# LCD.net
KiCad netlist of a schematic drawn in Altium Designer
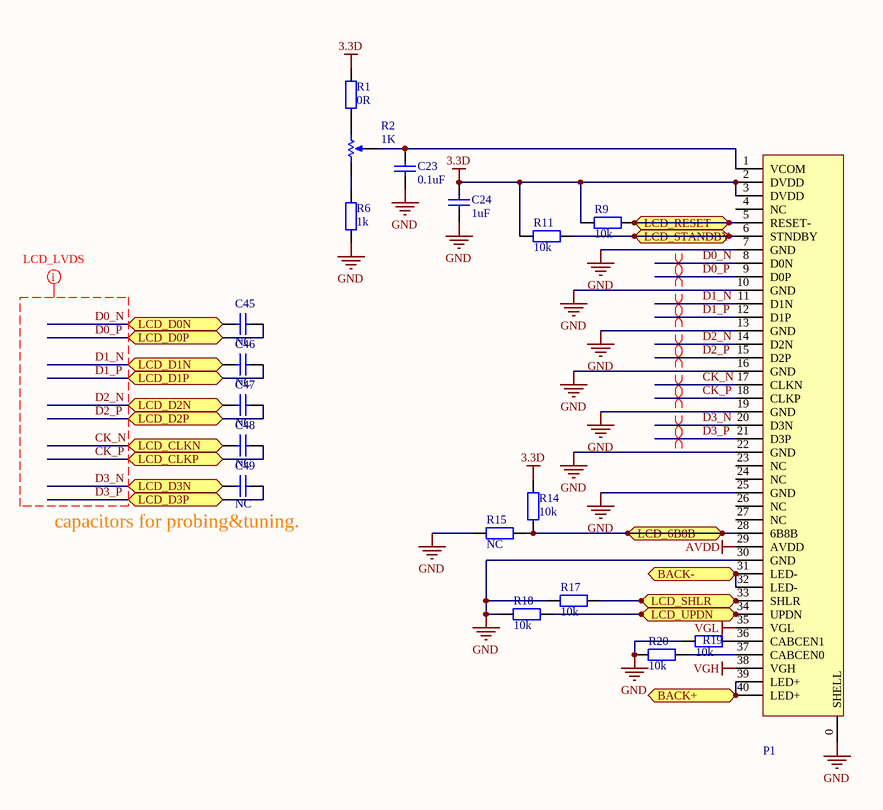
[diagram p0: LCD.SchDoc]

(export (version "E")
  (design (tool "Eeschema 10.0.6"))
  (components
    (comp (ref "C23")
      (value "0.1uF")
      (footprint "0402")
      (description "Capacitor")
      (fields (field (name "PUBLISHER") "Altium Limited"))
      (libsource (lib "RTC6705") (part "Cap"))
    )
    (comp (ref "C24")
      (value "1uF")
      (footprint "0402")
      (description "Capacitor")
      (fields (field (name "PUBLISHER") "Altium Limited"))
      (libsource (lib "RTC6705") (part "Cap"))
    )
    (comp (ref "C45")
      (value "NC")
      (footprint "0402")
      (description "Capacitor")
      (fields (field (name "PUBLISHER") "Altium Limited"))
      (libsource (lib "RTC6705") (part "Cap"))
    )
    (comp (ref "C46")
      (value "NC")
      (footprint "0402")
      (description "Capacitor")
      (fields (field (name "PUBLISHER") "Altium Limited"))
      (libsource (lib "RTC6705") (part "Cap"))
    )
    (comp (ref "C47")
      (value "NC")
      (footprint "0402")
      (description "Capacitor")
      (fields (field (name "PUBLISHER") "Altium Limited"))
      (libsource (lib "RTC6705") (part "Cap"))
    )
    (comp (ref "C48")
      (value "NC")
      (footprint "0402")
      (description "Capacitor")
      (fields (field (name "PUBLISHER") "Altium Limited"))
      (libsource (lib "RTC6705") (part "Cap"))
    )
    (comp (ref "C49")
      (value "NC")
      (footprint "0402")
      (description "Capacitor")
      (fields (field (name "PUBLISHER") "Altium Limited"))
      (libsource (lib "RTC6705") (part "Cap"))
    )
    (comp (ref "P1")
      (value "LCD_40P_LVDS")
      (footprint "FPC-0.5mm-40")
      (libsource (lib "sch") (part "LCD_40P_LVDS"))
    )
    (comp (ref "R1")
      (value "0R")
      (footprint "0402")
      (description "Resistor")
      (fields (field (name "PUBLISHER") "Altium Limited"))
      (libsource (lib "") (part "Res2_1"))
    )
    (comp (ref "R2")
      (value "1K")
      (footprint "POT1")
      (description "Potentiometer")
      (fields (field (name "Comment") "RPot") (field (name "PUBLISHER") "Altium Limited"))
      (libsource (lib "Miscellaneous Devices") (part "RPot"))
    )
    (comp (ref "R6")
      (value "1k")
      (footprint "0402")
      (description "Resistor")
      (fields (field (name "PUBLISHER") "Altium Limited"))
      (libsource (lib "") (part "Res2_1"))
    )
    (comp (ref "R9")
      (value "10k")
      (footprint "0402")
      (description "Resistor")
      (fields (field (name "PUBLISHER") "Altium Limited"))
      (libsource (lib "RTC6705") (part "Res2"))
    )
    (comp (ref "R11")
      (value "10k")
      (footprint "0402")
      (description "Resistor")
      (fields (field (name "PUBLISHER") "Altium Limited"))
      (libsource (lib "RTC6705") (part "Res2"))
    )
    (comp (ref "R14")
      (value "10k")
      (footprint "0402")
      (description "Resistor")
      (fields (field (name "PUBLISHER") "Altium Limited"))
      (libsource (lib "") (part "Res2_1"))
    )
    (comp (ref "R15")
      (value "NC")
      (footprint "0402")
      (description "Resistor")
      (fields (field (name "PUBLISHER") "Altium Limited"))
      (libsource (lib "RTC6705") (part "Res2"))
    )
    (comp (ref "R17")
      (value "10k")
      (footprint "0402")
      (description "Resistor")
      (fields (field (name "PUBLISHER") "Altium Limited"))
      (libsource (lib "RTC6705") (part "Res2"))
    )
    (comp (ref "R18")
      (value "10k")
      (footprint "0402")
      (description "Resistor")
      (fields (field (name "PUBLISHER") "Altium Limited"))
      (libsource (lib "RTC6705") (part "Res2"))
    )
    (comp (ref "R19")
      (value "10k")
      (footprint "0402")
      (description "Resistor")
      (fields (field (name "PUBLISHER") "Altium Limited"))
      (libsource (lib "RTC6705") (part "Res2"))
    )
    (comp (ref "R20")
      (value "10k")
      (footprint "0402")
      (description "Resistor")
      (fields (field (name "PUBLISHER") "Altium Limited"))
      (libsource (lib "RTC6705") (part "Res2"))
    )
  )
  (nets
    (net (code "1") (name "/BACK+") (class "Default")
      (node (ref "P1") (pin "39") (pinfunction "LED+_39") (pintype "passive"))
      (node (ref "P1") (pin "40") (pinfunction "LED+_40") (pintype "passive"))
    )
    (net (code "2") (name "/BACK-") (class "Default")
      (node (ref "P1") (pin "31") (pinfunction "LED-_31") (pintype "passive"))
      (node (ref "P1") (pin "32") (pinfunction "LED-_32") (pintype "passive"))
    )
    (net (code "3") (name "/CK_N") (class "Default")
      (node (ref "C48") (pin "1") (pinfunction "1_1") (pintype "passive"))
      (node (ref "P1") (pin "17") (pinfunction "CLKN_17") (pintype "passive"))
    )
    (net (code "4") (name "/CK_P") (class "Default")
      (node (ref "C48") (pin "2") (pinfunction "2_2") (pintype "passive"))
      (node (ref "P1") (pin "18") (pinfunction "CLKP_18") (pintype "passive"))
    )
    (net (code "5") (name "/D0_N") (class "Default")
      (node (ref "C45") (pin "1") (pinfunction "1_1") (pintype "passive"))
      (node (ref "P1") (pin "8") (pinfunction "D0N_8") (pintype "passive"))
    )
    (net (code "6") (name "/D0_P") (class "Default")
      (node (ref "C45") (pin "2") (pinfunction "2_2") (pintype "passive"))
      (node (ref "P1") (pin "9") (pinfunction "D0P_9") (pintype "passive"))
    )
    (net (code "7") (name "/D1_N") (class "Default")
      (node (ref "C46") (pin "1") (pinfunction "1_1") (pintype "passive"))
      (node (ref "P1") (pin "11") (pinfunction "D1N_11") (pintype "passive"))
    )
    (net (code "8") (name "/D1_P") (class "Default")
      (node (ref "C46") (pin "2") (pinfunction "2_2") (pintype "passive"))
      (node (ref "P1") (pin "12") (pinfunction "D1P_12") (pintype "passive"))
    )
    (net (code "9") (name "/D2_N") (class "Default")
      (node (ref "C47") (pin "1") (pinfunction "1_1") (pintype "passive"))
      (node (ref "P1") (pin "14") (pinfunction "D2N_14") (pintype "passive"))
    )
    (net (code "10") (name "/D2_P") (class "Default")
      (node (ref "C47") (pin "2") (pinfunction "2_2") (pintype "passive"))
      (node (ref "P1") (pin "15") (pinfunction "D2P_15") (pintype "passive"))
    )
    (net (code "11") (name "/D3_N") (class "Default")
      (node (ref "C49") (pin "1") (pinfunction "1_1") (pintype "passive"))
      (node (ref "P1") (pin "20") (pinfunction "D3N_20") (pintype "passive"))
    )
    (net (code "12") (name "/D3_P") (class "Default")
      (node (ref "C49") (pin "2") (pinfunction "2_2") (pintype "passive"))
      (node (ref "P1") (pin "21") (pinfunction "D3P_21") (pintype "passive"))
    )
    (net (code "13") (name "/LCD_6B8B") (class "Default")
      (node (ref "P1") (pin "28") (pinfunction "6B8B_28") (pintype "passive"))
      (node (ref "R14") (pin "1") (pinfunction "1_1") (pintype "passive"))
      (node (ref "R15") (pin "2") (pinfunction "2_2") (pintype "passive"))
    )
    (net (code "14") (name "/LCD_RESET") (class "Default")
      (node (ref "P1") (pin "5") (pinfunction "RESET-_5") (pintype "passive"))
      (node (ref "R9") (pin "2") (pinfunction "2_2") (pintype "passive"))
    )
    (net (code "15") (name "/LCD_SHLR") (class "Default")
      (node (ref "P1") (pin "33") (pinfunction "SHLR_33") (pintype "passive"))
      (node (ref "R17") (pin "2") (pinfunction "2_2") (pintype "passive"))
    )
    (net (code "16") (name "/LCD_STANDBY") (class "Default")
      (node (ref "P1") (pin "6") (pinfunction "STNDBY_6") (pintype "passive"))
      (node (ref "R11") (pin "2") (pinfunction "2_2") (pintype "passive"))
    )
    (net (code "17") (name "/LCD_UPDN") (class "Default")
      (node (ref "P1") (pin "34") (pinfunction "UPDN_34") (pintype "passive"))
      (node (ref "R18") (pin "2") (pinfunction "2_2") (pintype "passive"))
    )
    (net (code "18") (name "3.3D") (class "Default")
      (node (ref "C24") (pin "1") (pinfunction "1_1") (pintype "passive"))
      (node (ref "P1") (pin "2") (pinfunction "DVDD_2") (pintype "passive"))
      (node (ref "P1") (pin "3") (pinfunction "DVDD_3") (pintype "passive"))
      (node (ref "R1") (pin "2") (pinfunction "2_2") (pintype "passive"))
      (node (ref "R11") (pin "1") (pinfunction "1_1") (pintype "passive"))
      (node (ref "R14") (pin "2") (pinfunction "2_2") (pintype "passive"))
      (node (ref "R9") (pin "1") (pinfunction "1_1") (pintype "passive"))
    )
    (net (code "19") (name "AVDD") (class "Default")
      (node (ref "P1") (pin "29") (pinfunction "AVDD_29") (pintype "passive"))
    )
    (net (code "20") (name "GND") (class "Default")
      (node (ref "C23") (pin "2") (pinfunction "2_2") (pintype "passive"))
      (node (ref "C24") (pin "2") (pinfunction "2_2") (pintype "passive"))
      (node (ref "P1") (pin "0") (pinfunction "SHELL_0") (pintype "passive"))
      (node (ref "P1") (pin "10") (pinfunction "GND_10") (pintype "passive"))
      (node (ref "P1") (pin "13") (pinfunction "GND_13") (pintype "passive"))
      (node (ref "P1") (pin "16") (pinfunction "GND_16") (pintype "passive"))
      (node (ref "P1") (pin "19") (pinfunction "GND_19") (pintype "passive"))
      (node (ref "P1") (pin "22") (pinfunction "GND_22") (pintype "passive"))
      (node (ref "P1") (pin "25") (pinfunction "GND_25") (pintype "passive"))
      (node (ref "P1") (pin "30") (pinfunction "GND_30") (pintype "passive"))
      (node (ref "P1") (pin "7") (pinfunction "GND_7") (pintype "passive"))
      (node (ref "R15") (pin "1") (pinfunction "1_1") (pintype "passive"))
      (node (ref "R17") (pin "1") (pinfunction "1_1") (pintype "passive"))
      (node (ref "R18") (pin "1") (pinfunction "1_1") (pintype "passive"))
      (node (ref "R19") (pin "1") (pinfunction "1_1") (pintype "passive"))
      (node (ref "R20") (pin "1") (pinfunction "1_1") (pintype "passive"))
      (node (ref "R6") (pin "1") (pinfunction "1_1") (pintype "passive"))
    )
    (net (code "21") (name "Net-(P1-CABCEN0)") (class "Default")
      (node (ref "P1") (pin "37") (pinfunction "CABCEN0_37") (pintype "passive"))
      (node (ref "R20") (pin "2") (pinfunction "2_2") (pintype "passive"))
    )
    (net (code "22") (name "Net-(P1-CABCEN1)") (class "Default")
      (node (ref "P1") (pin "36") (pinfunction "CABCEN1_36") (pintype "passive"))
      (node (ref "R19") (pin "2") (pinfunction "2_2") (pintype "passive"))
    )
    (net (code "23") (name "Net-(P1-VCOM)") (class "Default")
      (node (ref "C23") (pin "1") (pinfunction "1_1") (pintype "passive"))
      (node (ref "P1") (pin "1") (pinfunction "VCOM_1") (pintype "passive"))
      (node (ref "R2") (pin "3") (pinfunction "TAP_3") (pintype "passive"))
    )
    (net (code "24") (name "Net-(R2-BOT)") (class "Default")
      (node (ref "R1") (pin "1") (pinfunction "1_1") (pintype "passive"))
      (node (ref "R2") (pin "2") (pinfunction "BOT_2") (pintype "passive"))
    )
    (net (code "25") (name "Net-(R2-TOP)") (class "Default")
      (node (ref "R2") (pin "1") (pinfunction "TOP_1") (pintype "passive"))
      (node (ref "R6") (pin "2") (pinfunction "2_2") (pintype "passive"))
    )
    (net (code "26") (name "VGH") (class "Default")
      (node (ref "P1") (pin "38") (pinfunction "VGH_38") (pintype "passive"))
    )
    (net (code "27") (name "VGL") (class "Default")
      (node (ref "P1") (pin "35") (pinfunction "VGL_35") (pintype "passive"))
    )
    (net (code "28") (name "unconnected-(P1-NC-Pad4)") (class "Default")
      (node (ref "P1") (pin "4") (pinfunction "NC_4") (pintype "passive"))
    )
    (net (code "29") (name "unconnected-(P1-NC-Pad23)") (class "Default")
      (node (ref "P1") (pin "23") (pinfunction "NC_23") (pintype "passive"))
    )
    (net (code "30") (name "unconnected-(P1-NC-Pad24)") (class "Default")
      (node (ref "P1") (pin "24") (pinfunction "NC_24") (pintype "passive"))
    )
    (net (code "31") (name "unconnected-(P1-NC-Pad26)") (class "Default")
      (node (ref "P1") (pin "26") (pinfunction "NC_26") (pintype "passive"))
    )
    (net (code "32") (name "unconnected-(P1-NC-Pad27)") (class "Default")
      (node (ref "P1") (pin "27") (pinfunction "NC_27") (pintype "passive"))
    )
  )
)
